# Pulse_Generator.net
KiCad netlist of a schematic drawn in Altium Designer
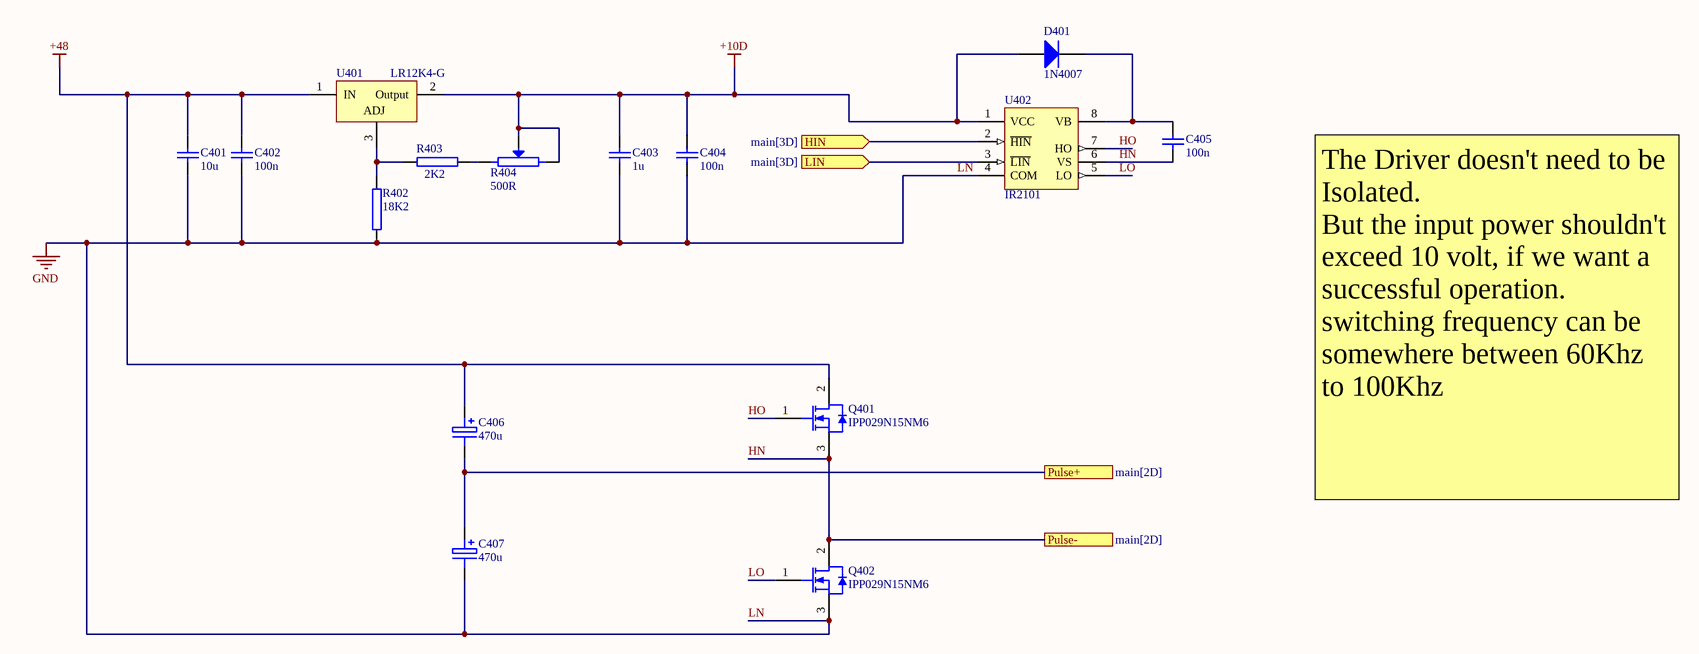
[diagram p0: Pulse_Generator.SchDoc]

(export (version "E")
  (design (tool "Eeschema 10.0.6"))
  (components
    (comp (ref "C401")
      (value "10u")
      (footprint "CAP_1206")
      (description "Non Polarized Capacitor, SMD, 1206")
      (libsource (lib "Resistors and Capacitors") (part "CAPN 1206"))
    )
    (comp (ref "C402")
      (value "100n")
      (footprint "CAP_1206")
      (description "Non Polarized Capacitor, SMD, 1206")
      (libsource (lib "Resistors and Capacitors") (part "CAPN 1206"))
    )
    (comp (ref "C403")
      (value "1u")
      (footprint "CAP_1206")
      (description "Non Polarized Capacitor, SMD, 1206")
      (libsource (lib "Resistors and Capacitors") (part "CAPN 1206"))
    )
    (comp (ref "C404")
      (value "100n")
      (footprint "CAP_1206")
      (description "Non Polarized Capacitor, SMD, 1206")
      (libsource (lib "Resistors and Capacitors") (part "CAPN 1206"))
    )
    (comp (ref "C405")
      (value "100n")
      (footprint "RAD-0.2_AUT")
      (description "Non Polarized Capacitor, Multilayer Ceramic Dipped Radial, Pitch 200mil")
      (libsource (lib "Resistors and Capacitors") (part "CAPN RAD0.2"))
    )
    (comp (ref "C406")
      (value "470u")
      (footprint "CAPP300-600_AUT")
      (description "Polarized Aluminum Capacitor, Through Hole, Pitch 300mil, Body 600mil (Dia)")
      (libsource (lib "Resistors and Capacitors") (part "CAPP300-600"))
    )
    (comp (ref "C407")
      (value "470u")
      (footprint "CAPP300-600_AUT")
      (description "Polarized Aluminum Capacitor, Through Hole, Pitch 300mil, Body 600mil (Dia)")
      (libsource (lib "Resistors and Capacitors") (part "CAPP300-600"))
    )
    (comp (ref "D401")
      (value "1N4007")
      (footprint "DIODE0.4_AUT")
      (description "Diode, Standard, 1A, 1000v")
      (libsource (lib "Diodes") (part "1N4007"))
    )
    (comp (ref "Q401")
      (value "IPP029N15NM6")
      (footprint "TO-220V")
      (libsource (lib "Projects_2021") (part "FQP65N06"))
    )
    (comp (ref "Q402")
      (value "IPP029N15NM6")
      (footprint "TO-220V")
      (libsource (lib "Projects_2021") (part "FQP65N06"))
    )
    (comp (ref "R402")
      (value "18K2")
      (footprint "RES_1206")
      (description "Resistor, SMD, 1206")
      (libsource (lib "Resistors and Capacitors") (part "Resistor 1206"))
    )
    (comp (ref "R403")
      (value "2K2")
      (footprint "RES_1206")
      (description "Resistor, SMD, 1206")
      (libsource (lib "Resistors and Capacitors") (part "Resistor 1206"))
    )
    (comp (ref "R404")
      (value "500R")
      (footprint "3296W")
      (libsource (lib "Potentiometers") (part "3296W-1-104LF"))
    )
    (comp (ref "U401")
      (value "LR12K4-G")
      (footprint "D PAK (TO-252-3)")
      (description "Adj Positive Regulator \r\nLinear. 12V dropout V. \r\n2W")
      (libsource (lib "Projects_2025") (part "LR12K4-G"))
    )
    (comp (ref "U402")
      (value "IR2101")
      (footprint "DIP8_AUT")
      (description "Half - Bridge Driver, MOSFET/IGBT, DIP8")
      (libsource (lib "Projects_2025") (part "IR2101_DIP"))
    )
  )
  (nets
    (net (code "1") (name "+10D") (class "Default")
      (node (ref "C403") (pin "2") (pinfunction "2_2") (pintype "passive"))
      (node (ref "C404") (pin "2") (pinfunction "2_2") (pintype "passive"))
      (node (ref "D401") (pin "A") (pinfunction "A_A") (pintype "passive"))
      (node (ref "R404") (pin "2") (pinfunction "BOT_2") (pintype "passive"))
      (node (ref "R404") (pin "W") (pinfunction "TAP_W") (pintype "passive"))
      (node (ref "U401") (pin "2") (pinfunction "Output_2") (pintype "power_in"))
      (node (ref "U402") (pin "1") (pinfunction "VCC_1") (pintype "power_in"))
    )
    (net (code "2") (name "+48") (class "Default")
      (node (ref "C401") (pin "2") (pinfunction "2_2") (pintype "passive"))
      (node (ref "C402") (pin "2") (pinfunction "2_2") (pintype "passive"))
      (node (ref "C406") (pin "1") (pinfunction "1_1") (pintype "passive"))
      (node (ref "Q401") (pin "2") (pinfunction "D_2") (pintype "passive"))
      (node (ref "U401") (pin "1") (pinfunction "IN_1") (pintype "power_in"))
    )
    (net (code "3") (name "/HIN") (class "Default")
      (node (ref "U402") (pin "2") (pinfunction "~{HIN}_2") (pintype "input"))
    )
    (net (code "4") (name "/HN") (class "Default")
      (node (ref "C405") (pin "1") (pinfunction "1_1") (pintype "passive"))
      (node (ref "Q401") (pin "3") (pinfunction "S_3") (pintype "passive"))
      (node (ref "Q402") (pin "2") (pinfunction "D_2") (pintype "passive"))
      (node (ref "U402") (pin "6") (pinfunction "VS_6") (pintype "power_in"))
    )
    (net (code "5") (name "/HO") (class "Default")
      (node (ref "Q401") (pin "1") (pinfunction "G_1") (pintype "passive"))
      (node (ref "U402") (pin "7") (pinfunction "HO_7") (pintype "output"))
    )
    (net (code "6") (name "/LIN") (class "Default")
      (node (ref "U402") (pin "3") (pinfunction "~{LIN}_3") (pintype "input"))
    )
    (net (code "7") (name "/LO") (class "Default")
      (node (ref "Q402") (pin "1") (pinfunction "G_1") (pintype "passive"))
      (node (ref "U402") (pin "5") (pinfunction "LO_5") (pintype "output"))
    )
    (net (code "8") (name "/Pulse+") (class "Default")
      (node (ref "C406") (pin "2") (pinfunction "2_2") (pintype "passive"))
      (node (ref "C407") (pin "1") (pinfunction "1_1") (pintype "passive"))
    )
    (net (code "9") (name "GND") (class "Default")
      (node (ref "C401") (pin "1") (pinfunction "1_1") (pintype "passive"))
      (node (ref "C402") (pin "1") (pinfunction "1_1") (pintype "passive"))
      (node (ref "C403") (pin "1") (pinfunction "1_1") (pintype "passive"))
      (node (ref "C404") (pin "1") (pinfunction "1_1") (pintype "passive"))
      (node (ref "C407") (pin "2") (pinfunction "2_2") (pintype "passive"))
      (node (ref "Q402") (pin "3") (pinfunction "S_3") (pintype "passive"))
      (node (ref "R402") (pin "1") (pinfunction "1_1") (pintype "passive"))
      (node (ref "U402") (pin "4") (pinfunction "COM_4") (pintype "power_in"))
    )
    (net (code "10") (name "Net-(R404-TOP)") (class "Default")
      (node (ref "R403") (pin "1") (pinfunction "1_1") (pintype "passive"))
      (node (ref "R404") (pin "1") (pinfunction "TOP_1") (pintype "passive"))
    )
    (net (code "11") (name "Net-(U401-ADJ)") (class "Default")
      (node (ref "R402") (pin "2") (pinfunction "2_2") (pintype "passive"))
      (node (ref "R403") (pin "2") (pinfunction "2_2") (pintype "passive"))
      (node (ref "U401") (pin "3") (pinfunction "ADJ_3") (pintype "power_in"))
    )
    (net (code "12") (name "Net-(U402-VB)") (class "Default")
      (node (ref "C405") (pin "2") (pinfunction "2_2") (pintype "passive"))
      (node (ref "D401") (pin "K") (pinfunction "K_K") (pintype "passive"))
      (node (ref "U402") (pin "8") (pinfunction "VB_8") (pintype "power_in"))
    )
  )
)
